# AccTop.net
KiCad netlist of a schematic drawn in Altium Designer
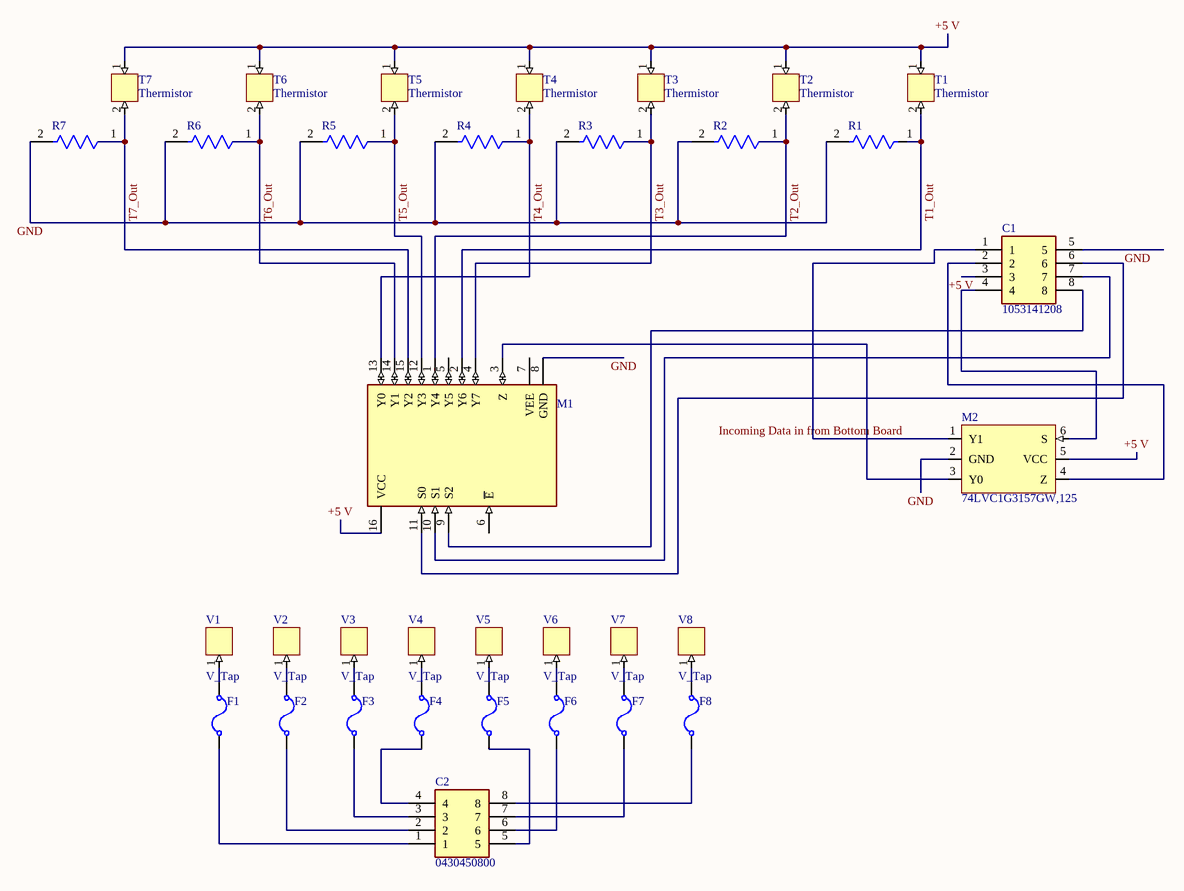
[diagram p0: AccTop.SchDoc]

(export (version "E")
  (design (tool "Eeschema 10.0.6"))
  (components
    (comp (ref "C1")
      (value "1053141208")
      (footprint "8 PIN DUAL NANO CONNECTOR")
      (libsource (lib "AccTop") (part "1053141208"))
    )
    (comp (ref "C2")
      (value "0430450800")
      (footprint "8 PIN DUAL CONNECTOR")
      (description "Rectangular Power Connector, 8 Contact(s), Male, Solder Terminal, Receptacle")
      (fields (field (name "MANUFACTURER") "Molex") (field (name "MANUFACTURER PART NUMBER") "43025-0800"))
      (libsource (lib "AccTop") (part "0430450800"))
    )
    (comp (ref "F1")
      (value "0ACG-1000-TE")
      (footprint "Fuse")
      (description "Electric Fuse, 1A, 350VAC, 500VDC, 100A (IR), Surface Mount")
      (fields (field (name "MANUFACTURER") "Bel"))
      (libsource (lib "AccTop") (part "0ACG-1000-TE"))
    )
    (comp (ref "F2")
      (value "0ACG-1000-TE")
      (footprint "Fuse")
      (description "Electric Fuse, 1A, 350VAC, 500VDC, 100A (IR), Surface Mount")
      (fields (field (name "MANUFACTURER") "Bel"))
      (libsource (lib "AccTop") (part "0ACG-1000-TE"))
    )
    (comp (ref "F3")
      (value "0ACG-1000-TE")
      (footprint "Fuse")
      (description "Electric Fuse, 1A, 350VAC, 500VDC, 100A (IR), Surface Mount")
      (fields (field (name "MANUFACTURER") "Bel"))
      (libsource (lib "AccTop") (part "0ACG-1000-TE"))
    )
    (comp (ref "F4")
      (value "0ACG-1000-TE")
      (footprint "Fuse")
      (description "Electric Fuse, 1A, 350VAC, 500VDC, 100A (IR), Surface Mount")
      (fields (field (name "MANUFACTURER") "Bel"))
      (libsource (lib "AccTop") (part "0ACG-1000-TE"))
    )
    (comp (ref "F5")
      (value "0ACG-1000-TE")
      (footprint "Fuse")
      (description "Electric Fuse, 1A, 350VAC, 500VDC, 100A (IR), Surface Mount")
      (fields (field (name "MANUFACTURER") "Bel"))
      (libsource (lib "AccTop") (part "0ACG-1000-TE"))
    )
    (comp (ref "F6")
      (value "0ACG-1000-TE")
      (footprint "Fuse")
      (description "Electric Fuse, 1A, 350VAC, 500VDC, 100A (IR), Surface Mount")
      (fields (field (name "MANUFACTURER") "Bel"))
      (libsource (lib "AccTop") (part "0ACG-1000-TE"))
    )
    (comp (ref "F7")
      (value "0ACG-1000-TE")
      (footprint "Fuse")
      (description "Electric Fuse, 1A, 350VAC, 500VDC, 100A (IR), Surface Mount")
      (fields (field (name "MANUFACTURER") "Bel"))
      (libsource (lib "AccTop") (part "0ACG-1000-TE"))
    )
    (comp (ref "F8")
      (value "0ACG-1000-TE")
      (footprint "Fuse")
      (description "Electric Fuse, 1A, 350VAC, 500VDC, 100A (IR), Surface Mount")
      (fields (field (name "MANUFACTURER") "Bel"))
      (libsource (lib "AccTop") (part "0ACG-1000-TE"))
    )
    (comp (ref "M1")
      (value "74HC4051D,653")
      (footprint "8x1MUX")
      (description "IC MUX/DEMUX 8X1 16SOIC")
      (libsource (lib "AccTop") (part "74HC4051D"))
    )
    (comp (ref "M2")
      (value "74LVC1G3157GW,125")
      (footprint "2x1MUX")
      (description "Single-Ended Multiplexer, 1 Func, 2 Channel, CMOS, PDSO6")
      (fields (field (name "MANUFACTURER") "Nexperia"))
      (libsource (lib "AccTop") (part "74LVC1G3157GW,125"))
    )
    (comp (ref "R1")
      (value "RC0805FR-133K3L")
      (footprint "3.3kRes")
      (fields
        (field (name "TOLERANCE") "1%")
        (field (name "MANUFACTURER") "KOA Speer")
        (field (name "MANUFACTURER PART NUMBER") "RK73G2ATTD3301F")
      )
      (libsource (lib "AccTop") (part "RC0805FR-133K3L"))
    )
    (comp (ref "R2")
      (value "RC0805FR-133K3L")
      (footprint "3.3kRes")
      (fields
        (field (name "TOLERANCE") "1%")
        (field (name "MANUFACTURER") "KOA Speer")
        (field (name "MANUFACTURER PART NUMBER") "RK73G2ATTD3301F")
      )
      (libsource (lib "AccTop") (part "RC0805FR-133K3L"))
    )
    (comp (ref "R3")
      (value "RC0805FR-133K3L")
      (footprint "3.3kRes")
      (fields
        (field (name "TOLERANCE") "1%")
        (field (name "MANUFACTURER") "KOA Speer")
        (field (name "MANUFACTURER PART NUMBER") "RK73G2ATTD3301F")
      )
      (libsource (lib "AccTop") (part "RC0805FR-133K3L"))
    )
    (comp (ref "R4")
      (value "RC0805FR-133K3L")
      (footprint "3.3kRes")
      (fields
        (field (name "TOLERANCE") "1%")
        (field (name "MANUFACTURER") "KOA Speer")
        (field (name "MANUFACTURER PART NUMBER") "RK73G2ATTD3301F")
      )
      (libsource (lib "AccTop") (part "RC0805FR-133K3L"))
    )
    (comp (ref "R5")
      (value "RC0805FR-133K3L")
      (footprint "3.3kRes")
      (fields
        (field (name "TOLERANCE") "1%")
        (field (name "MANUFACTURER") "KOA Speer")
        (field (name "MANUFACTURER PART NUMBER") "RK73G2ATTD3301F")
      )
      (libsource (lib "AccTop") (part "RC0805FR-133K3L"))
    )
    (comp (ref "R6")
      (value "RC0805FR-133K3L")
      (footprint "3.3kRes")
      (fields
        (field (name "TOLERANCE") "1%")
        (field (name "MANUFACTURER") "KOA Speer")
        (field (name "MANUFACTURER PART NUMBER") "RK73G2ATTD3301F")
      )
      (libsource (lib "AccTop") (part "RC0805FR-133K3L"))
    )
    (comp (ref "R7")
      (value "RC0805FR-133K3L")
      (footprint "3.3kRes")
      (fields
        (field (name "TOLERANCE") "1%")
        (field (name "MANUFACTURER") "KOA Speer")
        (field (name "MANUFACTURER PART NUMBER") "RK73G2ATTD3301F")
      )
      (libsource (lib "AccTop") (part "RC0805FR-133K3L"))
    )
    (comp (ref "T1")
      (value "Thermistor")
      (footprint "Thermistor")
      (libsource (lib "AccTop") (part "Thermistor"))
    )
    (comp (ref "T2")
      (value "Thermistor")
      (footprint "Thermistor")
      (libsource (lib "AccTop") (part "Thermistor"))
    )
    (comp (ref "T3")
      (value "Thermistor")
      (footprint "Thermistor")
      (libsource (lib "AccTop") (part "Thermistor"))
    )
    (comp (ref "T4")
      (value "Thermistor")
      (footprint "Thermistor")
      (libsource (lib "AccTop") (part "Thermistor"))
    )
    (comp (ref "T5")
      (value "Thermistor")
      (footprint "Thermistor")
      (libsource (lib "AccTop") (part "Thermistor"))
    )
    (comp (ref "T6")
      (value "Thermistor")
      (footprint "Thermistor")
      (libsource (lib "AccTop") (part "Thermistor"))
    )
    (comp (ref "T7")
      (value "Thermistor")
      (footprint "Thermistor")
      (libsource (lib "AccTop") (part "Thermistor"))
    )
    (comp (ref "V1") (value "V_Tap") (footprint "Voltage tap") (libsource (lib "AccTop") (part "V_Tap")))
    (comp (ref "V2") (value "V_Tap") (footprint "Voltage tap") (libsource (lib "AccTop") (part "V_Tap")))
    (comp (ref "V3") (value "V_Tap") (footprint "Voltage tap") (libsource (lib "AccTop") (part "V_Tap")))
    (comp (ref "V4") (value "V_Tap") (footprint "Voltage tap") (libsource (lib "AccTop") (part "V_Tap")))
    (comp (ref "V5") (value "V_Tap") (footprint "Voltage tap") (libsource (lib "AccTop") (part "V_Tap")))
    (comp (ref "V6") (value "V_Tap") (footprint "Voltage tap") (libsource (lib "AccTop") (part "V_Tap")))
    (comp (ref "V7") (value "V_Tap") (footprint "Voltage tap") (libsource (lib "AccTop") (part "V_Tap")))
    (comp (ref "V8") (value "V_Tap") (footprint "Voltage tap") (libsource (lib "AccTop") (part "V_Tap")))
  )
  (nets
    (net (code "1") (name "/+5 V") (class "Default")
      (node (ref "C1") (pin "3") (pinfunction "3_3") (pintype "passive"))
      (node (ref "M1") (pin "16") (pinfunction "VCC_16") (pintype "power_in"))
      (node (ref "M2") (pin "5") (pinfunction "VCC_5") (pintype "open_collector"))
      (node (ref "T1") (pin "1") (pintype "input"))
      (node (ref "T2") (pin "1") (pintype "input"))
      (node (ref "T3") (pin "1") (pintype "input"))
      (node (ref "T4") (pin "1") (pintype "input"))
      (node (ref "T5") (pin "1") (pintype "input"))
      (node (ref "T6") (pin "1") (pintype "input"))
      (node (ref "T7") (pin "1") (pintype "input"))
    )
    (net (code "2") (name "/GND") (class "Default")
      (node (ref "C1") (pin "5") (pinfunction "5_5") (pintype "passive"))
      (node (ref "M1") (pin "8") (pinfunction "GND_8") (pintype "power_in"))
      (node (ref "M2") (pin "2") (pinfunction "GND_2") (pintype "open_collector"))
      (node (ref "R1") (pin "2") (pinfunction "2_2") (pintype "passive"))
      (node (ref "R2") (pin "2") (pinfunction "2_2") (pintype "passive"))
      (node (ref "R3") (pin "2") (pinfunction "2_2") (pintype "passive"))
      (node (ref "R4") (pin "2") (pinfunction "2_2") (pintype "passive"))
      (node (ref "R5") (pin "2") (pinfunction "2_2") (pintype "passive"))
      (node (ref "R6") (pin "2") (pinfunction "2_2") (pintype "passive"))
      (node (ref "R7") (pin "2") (pinfunction "2_2") (pintype "passive"))
    )
    (net (code "4") (name "/T1_Out") (class "Default")
      (node (ref "M1") (pin "2") (pinfunction "Y6_2") (pintype "bidirectional"))
      (node (ref "R1") (pin "1") (pinfunction "1_1") (pintype "passive"))
      (node (ref "T1") (pin "2") (pintype "input"))
    )
    (net (code "5") (name "/T2_Out") (class "Default")
      (node (ref "M1") (pin "1") (pinfunction "Y4_1") (pintype "bidirectional"))
      (node (ref "R2") (pin "1") (pinfunction "1_1") (pintype "passive"))
      (node (ref "T2") (pin "2") (pintype "input"))
    )
    (net (code "6") (name "/T3_Out") (class "Default")
      (node (ref "M1") (pin "4") (pinfunction "Y7_4") (pintype "bidirectional"))
      (node (ref "R3") (pin "1") (pinfunction "1_1") (pintype "passive"))
      (node (ref "T3") (pin "2") (pintype "input"))
    )
    (net (code "7") (name "/T4_Out") (class "Default")
      (node (ref "M1") (pin "13") (pinfunction "Y0_13") (pintype "bidirectional"))
      (node (ref "R4") (pin "1") (pinfunction "1_1") (pintype "passive"))
      (node (ref "T4") (pin "2") (pintype "input"))
    )
    (net (code "8") (name "/T5_Out") (class "Default")
      (node (ref "M1") (pin "12") (pinfunction "Y3_12") (pintype "bidirectional"))
      (node (ref "R5") (pin "1") (pinfunction "1_1") (pintype "passive"))
      (node (ref "T5") (pin "2") (pintype "input"))
    )
    (net (code "9") (name "/T6_Out") (class "Default")
      (node (ref "M1") (pin "14") (pinfunction "Y1_14") (pintype "bidirectional"))
      (node (ref "R6") (pin "1") (pinfunction "1_1") (pintype "passive"))
      (node (ref "T6") (pin "2") (pintype "input"))
    )
    (net (code "10") (name "/T7_Out") (class "Default")
      (node (ref "M1") (pin "15") (pinfunction "Y2_15") (pintype "bidirectional"))
      (node (ref "R7") (pin "1") (pinfunction "1_1") (pintype "passive"))
      (node (ref "T7") (pin "2") (pintype "input"))
    )
    (net (code "11") (name "Net-(C2-Pad1)") (class "Default")
      (node (ref "C2") (pin "1") (pinfunction "1_1") (pintype "passive"))
      (node (ref "F1") (pin "1") (pinfunction "PB6_1") (pintype "passive"))
    )
    (net (code "12") (name "Net-(C2-Pad2)") (class "Default")
      (node (ref "C2") (pin "2") (pinfunction "2_2") (pintype "passive"))
      (node (ref "F2") (pin "1") (pinfunction "PB6_1") (pintype "passive"))
    )
    (net (code "13") (name "Net-(C2-Pad3)") (class "Default")
      (node (ref "C2") (pin "3") (pinfunction "3_3") (pintype "passive"))
      (node (ref "F3") (pin "1") (pinfunction "PB6_1") (pintype "passive"))
    )
    (net (code "14") (name "Net-(C2-Pad4)") (class "Default")
      (node (ref "C2") (pin "4") (pinfunction "4_4") (pintype "passive"))
      (node (ref "F4") (pin "1") (pinfunction "PB6_1") (pintype "passive"))
    )
    (net (code "15") (name "Net-(C2-Pad5)") (class "Default")
      (node (ref "C2") (pin "5") (pinfunction "5_5") (pintype "passive"))
      (node (ref "F5") (pin "1") (pinfunction "PB6_1") (pintype "passive"))
    )
    (net (code "16") (name "Net-(C2-Pad6)") (class "Default")
      (node (ref "C2") (pin "6") (pinfunction "6_6") (pintype "passive"))
      (node (ref "F6") (pin "1") (pinfunction "PB6_1") (pintype "passive"))
    )
    (net (code "17") (name "Net-(C2-Pad7)") (class "Default")
      (node (ref "C2") (pin "7") (pinfunction "7_7") (pintype "passive"))
      (node (ref "F7") (pin "1") (pinfunction "PB6_1") (pintype "passive"))
    )
    (net (code "18") (name "Net-(C2-Pad8)") (class "Default")
      (node (ref "C2") (pin "8") (pinfunction "8_8") (pintype "passive"))
      (node (ref "F8") (pin "1") (pinfunction "PB6_1") (pintype "passive"))
    )
    (net (code "19") (name "Net-(F1-PB6-Pad2)") (class "Default")
      (node (ref "F1") (pin "2") (pinfunction "PB6_2") (pintype "passive"))
      (node (ref "V1") (pin "1") (pintype "input"))
    )
    (net (code "20") (name "Net-(F2-PB6-Pad2)") (class "Default")
      (node (ref "F2") (pin "2") (pinfunction "PB6_2") (pintype "passive"))
      (node (ref "V2") (pin "1") (pintype "input"))
    )
    (net (code "21") (name "Net-(F3-PB6-Pad2)") (class "Default")
      (node (ref "F3") (pin "2") (pinfunction "PB6_2") (pintype "passive"))
      (node (ref "V3") (pin "1") (pintype "input"))
    )
    (net (code "22") (name "Net-(F4-PB6-Pad2)") (class "Default")
      (node (ref "F4") (pin "2") (pinfunction "PB6_2") (pintype "passive"))
      (node (ref "V4") (pin "1") (pintype "input"))
    )
    (net (code "23") (name "Net-(F5-PB6-Pad2)") (class "Default")
      (node (ref "F5") (pin "2") (pinfunction "PB6_2") (pintype "passive"))
      (node (ref "V5") (pin "1") (pintype "input"))
    )
    (net (code "24") (name "Net-(F6-PB6-Pad2)") (class "Default")
      (node (ref "F6") (pin "2") (pinfunction "PB6_2") (pintype "passive"))
      (node (ref "V6") (pin "1") (pintype "input"))
    )
    (net (code "25") (name "Net-(F7-PB6-Pad2)") (class "Default")
      (node (ref "F7") (pin "2") (pinfunction "PB6_2") (pintype "passive"))
      (node (ref "V7") (pin "1") (pintype "input"))
    )
    (net (code "26") (name "Net-(F8-PB6-Pad2)") (class "Default")
      (node (ref "F8") (pin "2") (pinfunction "PB6_2") (pintype "passive"))
      (node (ref "V8") (pin "1") (pintype "input"))
    )
    (net (code "27") (name "Net-(M1-S0)") (class "Default")
      (node (ref "C1") (pin "6") (pinfunction "6_6") (pintype "passive"))
      (node (ref "M1") (pin "11") (pinfunction "S0_11") (pintype "input"))
    )
    (net (code "28") (name "Net-(M1-S1)") (class "Default")
      (node (ref "C1") (pin "7") (pinfunction "7_7") (pintype "passive"))
      (node (ref "M1") (pin "10") (pinfunction "S1_10") (pintype "input"))
    )
    (net (code "29") (name "Net-(M1-S2)") (class "Default")
      (node (ref "C1") (pin "8") (pinfunction "8_8") (pintype "passive"))
      (node (ref "M1") (pin "9") (pinfunction "S2_9") (pintype "input"))
    )
    (net (code "30") (name "Net-(M1-Z)") (class "Default")
      (node (ref "M1") (pin "3") (pinfunction "Z_3") (pintype "bidirectional"))
      (node (ref "M2") (pin "3") (pinfunction "Y0_3") (pintype "bidirectional"))
    )
    (net (code "31") (name "Net-(M2-S)") (class "Default")
      (node (ref "C1") (pin "4") (pinfunction "4_4") (pintype "passive"))
      (node (ref "M2") (pin "6") (pinfunction "S_6") (pintype "input"))
    )
    (net (code "32") (name "Net-(M2-Y1)") (class "Default")
      (node (ref "C1") (pin "1") (pinfunction "1_1") (pintype "passive"))
      (node (ref "M2") (pin "1") (pinfunction "Y1_1") (pintype "bidirectional"))
    )
    (net (code "33") (name "Net-(M2-Z)") (class "Default")
      (node (ref "C1") (pin "2") (pinfunction "2_2") (pintype "passive"))
      (node (ref "M2") (pin "4") (pinfunction "Z_4") (pintype "bidirectional"))
    )
    (net (code "34") (name "unconnected-(M1-VEE-Pad7)") (class "Default")
      (node (ref "M1") (pin "7") (pinfunction "VEE_7") (pintype "power_in"))
    )
    (net (code "35") (name "unconnected-(M1-Y5-Pad5)") (class "Default")
      (node (ref "M1") (pin "5") (pinfunction "Y5_5") (pintype "bidirectional"))
    )
    (net (code "36") (name "unconnected-(M1-~{E}-Pad6)") (class "Default")
      (node (ref "M1") (pin "6") (pinfunction "~{E}_6") (pintype "input"))
    )
  )
)
